# design.net
KiCad netlist of a schematic drawn in Altium Designer
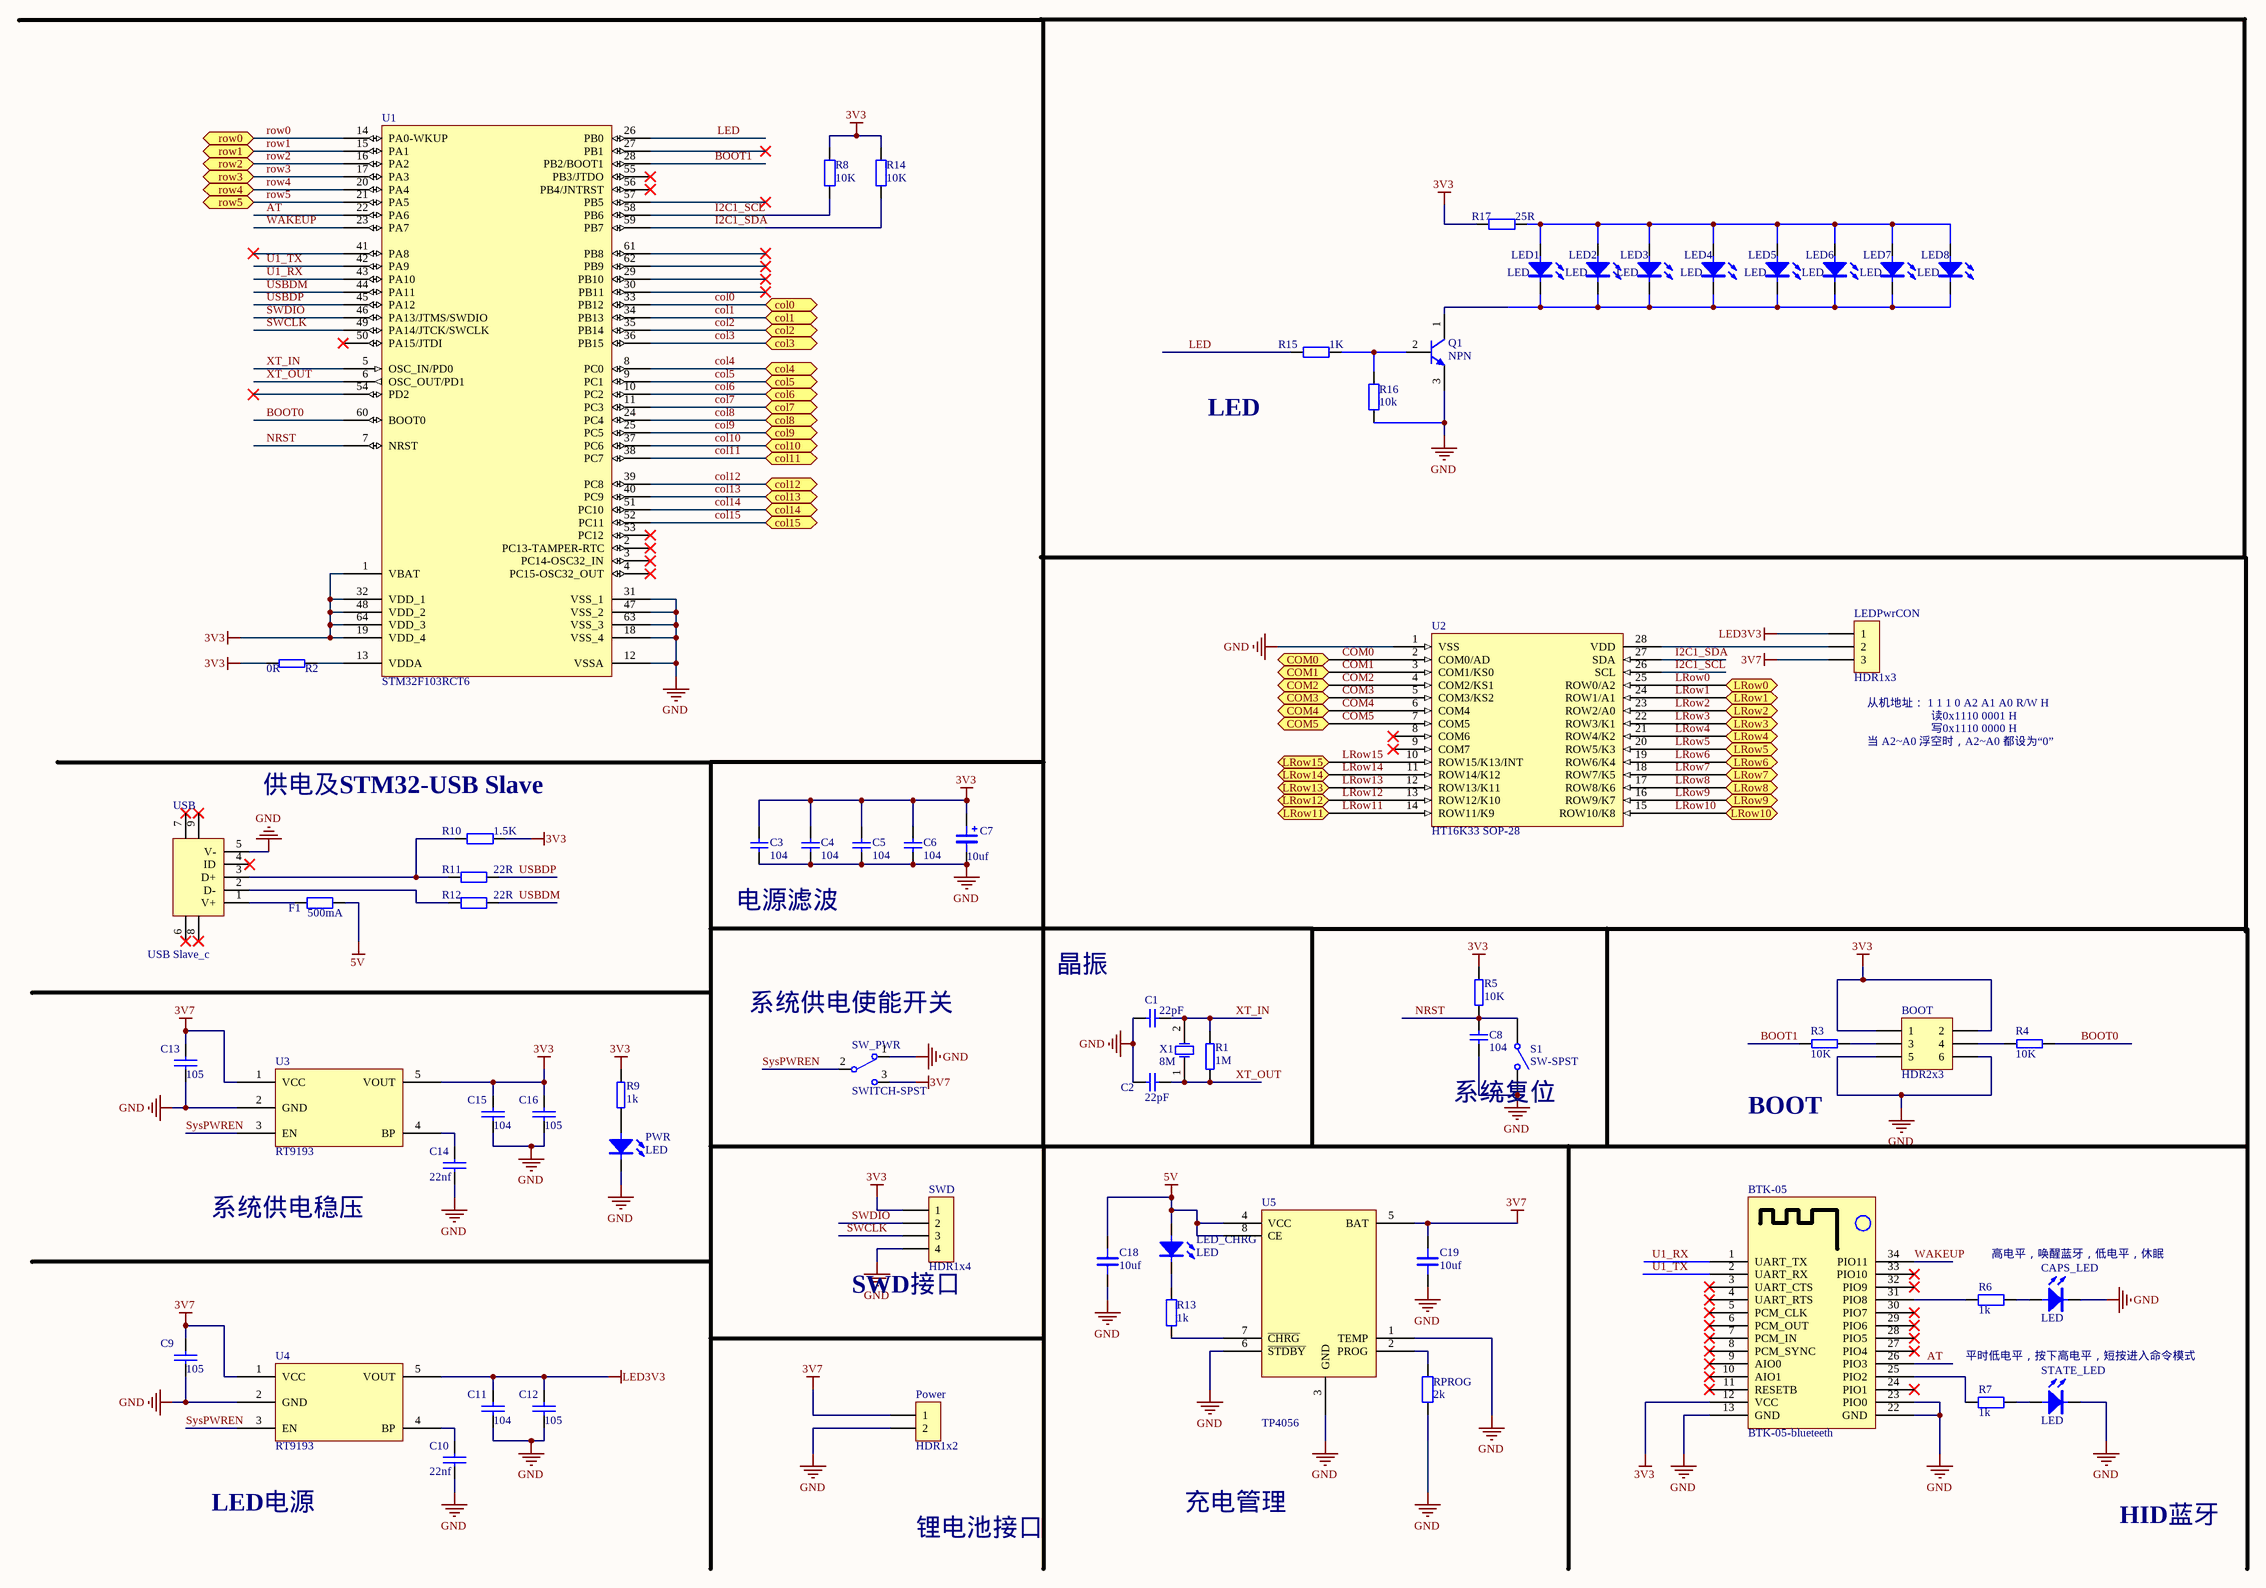
[diagram p0: 创世一号_主控.SchDoc]

(export (version "E")
  (design (tool "Eeschema 10.0.6"))
  (components
    (comp (ref "BOOT")
      (value "HDR2x3")
      (footprint "PIN-2x3-2.54-1.0")
      (description "Connector")
      (libsource (lib "General") (part "HDR2x3"))
    )
    (comp (ref "BTK-05")
      (value "BTK-05-blueteeth")
      (footprint "BTK-05-bluteeth")
      (libsource (lib "MyLib") (part "BTK-05-blueteeth"))
    )
    (comp (ref "C1")
      (value "22pF")
      (footprint "RC0603")
      (description "Capacitor")
      (fields (field (name "PUBLISHER") "ZL_A0OFFICE"))
      (libsource (lib "CommomDevices") (part "CAP1"))
    )
    (comp (ref "C2")
      (value "22pF")
      (footprint "RC0603")
      (description "Capacitor")
      (fields (field (name "PUBLISHER") "ZL_A0OFFICE"))
      (libsource (lib "CommomDevices") (part "CAP1"))
    )
    (comp (ref "C3")
      (value "104")
      (footprint "RC0603")
      (description "Capacitor")
      (fields (field (name "PUBLISHER") "ZL_A0OFFICE"))
      (libsource (lib "CommomDevices") (part "CAP1"))
    )
    (comp (ref "C4")
      (value "104")
      (footprint "RC0603")
      (description "Capacitor")
      (fields (field (name "PUBLISHER") "ZL_A0OFFICE"))
      (libsource (lib "CommomDevices") (part "CAP1"))
    )
    (comp (ref "C5")
      (value "104")
      (footprint "RC0603")
      (description "Capacitor")
      (fields (field (name "PUBLISHER") "ZL_A0OFFICE"))
      (libsource (lib "CommomDevices") (part "CAP1"))
    )
    (comp (ref "C6")
      (value "104")
      (footprint "RC0603")
      (description "Capacitor")
      (fields (field (name "PUBLISHER") "ZL_A0OFFICE"))
      (libsource (lib "CommomDevices") (part "CAP1"))
    )
    (comp (ref "C7")
      (value "10uf")
      (footprint "CAP0805")
      (description "Tantalum Capacitor")
      (libsource (lib "General") (part "CAP-TANTALUM"))
    )
    (comp (ref "C8")
      (value "104")
      (footprint "RC0603")
      (description "Capacitor")
      (fields (field (name "PUBLISHER") "ZL_A0OFFICE"))
      (libsource (lib "CommomDevices") (part "CAP1"))
    )
    (comp (ref "C9")
      (value "105")
      (footprint "0603")
      (description "Capacitor")
      (libsource (lib "*") (part "CAP"))
    )
    (comp (ref "C10")
      (value "22nf")
      (footprint "0603")
      (description "Capacitor")
      (libsource (lib "*") (part "CAP"))
    )
    (comp (ref "C11")
      (value "104")
      (footprint "0603")
      (description "Capacitor")
      (libsource (lib "*") (part "CAP"))
    )
    (comp (ref "C12")
      (value "105")
      (footprint "0603")
      (description "Capacitor")
      (libsource (lib "*") (part "CAP"))
    )
    (comp (ref "C13")
      (value "105")
      (footprint "0603")
      (description "Capacitor")
      (libsource (lib "*") (part "CAP"))
    )
    (comp (ref "C14")
      (value "22nf")
      (footprint "0603")
      (description "Capacitor")
      (libsource (lib "*") (part "CAP"))
    )
    (comp (ref "C15")
      (value "104")
      (footprint "0603")
      (description "Capacitor")
      (libsource (lib "*") (part "CAP"))
    )
    (comp (ref "C16")
      (value "105")
      (footprint "0603")
      (description "Capacitor")
      (libsource (lib "*") (part "CAP"))
    )
    (comp (ref "C18")
      (value "10uf")
      (footprint "0805")
      (description "Capacitor")
      (libsource (lib "General") (part "CAP"))
    )
    (comp (ref "C19")
      (value "10uf")
      (footprint "0805")
      (description "Capacitor")
      (libsource (lib "General") (part "CAP"))
    )
    (comp (ref "CAPS_LED") (value "LED") (footprint "LED-0805") (libsource (lib "General") (part "LED")))
    (comp (ref "F1")
      (value "500mA")
      (footprint "0805")
      (description "Resistor")
      (libsource (lib "") (part "Res2_1"))
    )
    (comp (ref "LED1") (value "LED") (footprint "LED-0805") (libsource (lib "General") (part "LED")))
    (comp (ref "LED2") (value "LED") (footprint "LED-0805") (libsource (lib "General") (part "LED")))
    (comp (ref "LED3") (value "LED") (footprint "LED-0805") (libsource (lib "General") (part "LED")))
    (comp (ref "LED4") (value "LED") (footprint "LED-0805") (libsource (lib "General") (part "LED")))
    (comp (ref "LED5") (value "LED") (footprint "LED-0805") (libsource (lib "General") (part "LED")))
    (comp (ref "LED6") (value "LED") (footprint "LED-0805") (libsource (lib "General") (part "LED")))
    (comp (ref "LED7") (value "LED") (footprint "LED-0805") (libsource (lib "General") (part "LED")))
    (comp (ref "LED8") (value "LED") (footprint "LED-0805") (libsource (lib "General") (part "LED")))
    (comp (ref "LEDPwrCON")
      (value "HDR1x3")
      (footprint "PIN-3-2.54-1.0")
      (description "Connector")
      (libsource (lib "General") (part "HDR1x3"))
    )
    (comp (ref "LED_CHRG") (value "LED") (footprint "LED-0805") (libsource (lib "General") (part "LED")))
    (comp (ref "Power")
      (value "HDR1x2")
      (footprint "PIN-2-2.54-1.0")
      (description "Connector")
      (libsource (lib "General") (part "HDR1x2"))
    )
    (comp (ref "PWR") (value "LED") (footprint "LED-0805") (libsource (lib "General") (part "LED")))
    (comp (ref "Q1")
      (value "NPN")
      (footprint "S8050-TO-92")
      (description "NPN Bipolar Transistor")
      (fields (field (name "PUBLISHER") "Altium Limited"))
      (libsource (lib "Miscellaneous Devices") (part "NPN"))
    )
    (comp (ref "R1") (value "1M") (footprint "RC0603") (libsource (lib "ZIBO V2.0_Main") (part "R")))
    (comp (ref "R2") (value "0R") (footprint "RC0603") (libsource (lib "ZIBO V2.0_Main") (part "R")))
    (comp (ref "R3") (value "10K") (footprint "RC0603") (libsource (lib "ZIBO V2.0_Main") (part "R")))
    (comp (ref "R4") (value "10K") (footprint "RC0603") (libsource (lib "ZIBO V2.0_Main") (part "R")))
    (comp (ref "R5") (value "10K") (footprint "RC0603") (libsource (lib "ZIBO V2.0_Main") (part "R")))
    (comp (ref "R6")
      (value "1k")
      (footprint "0603")
      (description "Resistor")
      (libsource (lib "") (part "RES_1"))
    )
    (comp (ref "R7")
      (value "1k")
      (footprint "0603")
      (description "Resistor")
      (libsource (lib "") (part "RES_1"))
    )
    (comp (ref "R8")
      (value "10K")
      (footprint "0603")
      (description "Resistor")
      (libsource (lib "") (part "Res2_2"))
    )
    (comp (ref "R9") (value "1k") (footprint "0603") (libsource (lib "ZIBO V2.0_Main") (part "R")))
    (comp (ref "R10")
      (value "1.5K")
      (footprint "0603")
      (description "Resistor")
      (libsource (lib "Miscellaneous Devices") (part "Res2"))
    )
    (comp (ref "R11")
      (value "22R")
      (footprint "0603")
      (description "Resistor")
      (libsource (lib "Miscellaneous Devices") (part "Res2"))
    )
    (comp (ref "R12")
      (value "22R")
      (footprint "0603")
      (description "Resistor")
      (libsource (lib "Miscellaneous Devices") (part "Res2"))
    )
    (comp (ref "R13")
      (value "1k")
      (footprint "0603")
      (description "Resistor")
      (libsource (lib "General") (part "RES"))
    )
    (comp (ref "R14")
      (value "10K")
      (footprint "0603")
      (description "Resistor")
      (libsource (lib "") (part "Res2_2"))
    )
    (comp (ref "R15")
      (value "1K")
      (footprint "0603")
      (description "Resistor")
      (libsource (lib "Miscellaneous Devices") (part "Res2"))
    )
    (comp (ref "R16")
      (value "10k")
      (footprint "0603")
      (description "Resistor")
      (libsource (lib "") (part "Res2_2"))
    )
    (comp (ref "R17")
      (value "25R")
      (footprint "0603")
      (description "Resistor")
      (libsource (lib "Miscellaneous Devices") (part "Res2"))
    )
    (comp (ref "RPROG")
      (value "2k")
      (footprint "0603")
      (description "Resistor")
      (libsource (lib "General") (part "RES"))
    )
    (comp (ref "S1")
      (value "SW-SPST")
      (footprint "SMT-KEY")
      (description "Single-Pole, Single-Throw Switch")
      (libsource (lib "Miscellaneous Devices") (part "SW-SPST"))
    )
    (comp (ref "STATE_LED") (value "LED") (footprint "LED-0805") (libsource (lib "General") (part "LED")))
    (comp (ref "SWD")
      (value "HDR1x4")
      (footprint "PIN-4-2.54-1.0")
      (description "Connector")
      (libsource (lib "General") (part "HDR1x4"))
    )
    (comp (ref "SW_PWR")
      (value "SWITCH-SPST")
      (footprint "Switch_3p_2.5mmjianju")
      (description "Switch")
      (libsource (lib "General") (part "SWITCH-SPST"))
    )
    (comp (ref "U1")
      (value "STM32F103RCT6")
      (footprint "QFP-64-0.5")
      (description "MCU")
      (libsource (lib "General") (part "STM32F103RxTx"))
    )
    (comp (ref "U2")
      (value "HT16K33 SOP-28")
      (footprint "HT16K33-28PIN-SOP28")
      (libsource (lib "MyLib") (part "HT16K33 SOP-28"))
    )
    (comp (ref "U3") (value "RT9193") (footprint "SOT-23-5") (libsource (lib "MyLib") (part "RT9193")))
    (comp (ref "U4") (value "RT9193") (footprint "SOT-23-5") (libsource (lib "MyLib") (part "RT9193")))
    (comp (ref "U5") (value "TP4056") (footprint "ESOP8") (libsource (lib "MyLib") (part "TP4056")))
    (comp (ref "USB")
      (value "USB Slave_c")
      (footprint "MICRO USB CONNECTOR TYPEB-ST-MC-5F-01")
      (description "USB Connector")
      (libsource (lib "General") (part "MICRO USB CONNECTOR TYPEB"))
    )
    (comp (ref "X1")
      (value "8M")
      (footprint "HC49-SMD")
      (description "Crystal Oscillator")
      (fields (field (name "PUBLISHER") "ZL_A0OFFICE"))
      (libsource (lib "CommomDevices") (part "XTAL_SMD"))
    )
  )
  (nets
    (net (code "1") (name "/AT") (class "Default")
      (node (ref "BTK-05") (pin "26") (pinfunction "PIO3_26") (pintype "passive"))
      (node (ref "U1") (pin "22") (pinfunction "PA6_22") (pintype "bidirectional"))
    )
    (net (code "2") (name "/BOOT0") (class "Default")
      (node (ref "R4") (pin "1") (pinfunction "1_1") (pintype "passive"))
      (node (ref "U1") (pin "60") (pinfunction "BOOT0_60") (pintype "bidirectional"))
    )
    (net (code "3") (name "/BOOT1") (class "Default")
      (node (ref "R3") (pin "2") (pinfunction "2_2") (pintype "passive"))
      (node (ref "U1") (pin "28") (pinfunction "PB2/BOOT1_28") (pintype "bidirectional"))
    )
    (net (code "4") (name "/COM0") (class "Default")
      (node (ref "U2") (pin "2") (pinfunction "COM0/AD_2") (pintype "input"))
    )
    (net (code "5") (name "/COM1") (class "Default")
      (node (ref "U2") (pin "3") (pinfunction "COM1/KS0_3") (pintype "input"))
    )
    (net (code "6") (name "/COM2") (class "Default")
      (node (ref "U2") (pin "4") (pinfunction "COM2/KS1_4") (pintype "input"))
    )
    (net (code "7") (name "/COM3") (class "Default")
      (node (ref "U2") (pin "5") (pinfunction "COM3/KS2_5") (pintype "input"))
    )
    (net (code "8") (name "/COM4") (class "Default")
      (node (ref "U2") (pin "6") (pinfunction "COM4_6") (pintype "input"))
    )
    (net (code "9") (name "/COM5") (class "Default")
      (node (ref "U2") (pin "7") (pinfunction "COM5_7") (pintype "input"))
    )
    (net (code "10") (name "/I2C1_SCL") (class "Default")
      (node (ref "R8") (pin "2") (pinfunction "2_2") (pintype "passive"))
      (node (ref "U1") (pin "58") (pinfunction "PB6_58") (pintype "bidirectional"))
      (node (ref "U2") (pin "26") (pinfunction "SCL_26") (pintype "input"))
    )
    (net (code "11") (name "/I2C1_SDA") (class "Default")
      (node (ref "R14") (pin "2") (pinfunction "2_2") (pintype "passive"))
      (node (ref "U1") (pin "59") (pinfunction "PB7_59") (pintype "bidirectional"))
      (node (ref "U2") (pin "27") (pinfunction "SDA_27") (pintype "input"))
    )
    (net (code "12") (name "/LED") (class "Default")
      (node (ref "R15") (pin "2") (pinfunction "2_2") (pintype "passive"))
      (node (ref "U1") (pin "26") (pinfunction "PB0_26") (pintype "bidirectional"))
    )
    (net (code "13") (name "/LRow0") (class "Default")
      (node (ref "U2") (pin "25") (pinfunction "ROW0/A2_25") (pintype "input"))
    )
    (net (code "14") (name "/LRow1") (class "Default")
      (node (ref "U2") (pin "24") (pinfunction "ROW1/A1_24") (pintype "input"))
    )
    (net (code "15") (name "/LRow2") (class "Default")
      (node (ref "U2") (pin "23") (pinfunction "ROW2/A0_23") (pintype "input"))
    )
    (net (code "16") (name "/LRow3") (class "Default")
      (node (ref "U2") (pin "22") (pinfunction "ROW3/K1_22") (pintype "input"))
    )
    (net (code "17") (name "/LRow4") (class "Default")
      (node (ref "U2") (pin "21") (pinfunction "ROW4/K2_21") (pintype "input"))
    )
    (net (code "18") (name "/LRow5") (class "Default")
      (node (ref "U2") (pin "20") (pinfunction "ROW5/K3_20") (pintype "input"))
    )
    (net (code "19") (name "/LRow6") (class "Default")
      (node (ref "U2") (pin "19") (pinfunction "ROW6/K4_19") (pintype "input"))
    )
    (net (code "20") (name "/LRow7") (class "Default")
      (node (ref "U2") (pin "18") (pinfunction "ROW7/K5_18") (pintype "input"))
    )
    (net (code "21") (name "/LRow8") (class "Default")
      (node (ref "U2") (pin "17") (pinfunction "ROW8/K6_17") (pintype "input"))
    )
    (net (code "22") (name "/LRow9") (class "Default")
      (node (ref "U2") (pin "16") (pinfunction "ROW9/K7_16") (pintype "input"))
    )
    (net (code "23") (name "/LRow10") (class "Default")
      (node (ref "U2") (pin "15") (pinfunction "ROW10/K8_15") (pintype "input"))
    )
    (net (code "24") (name "/LRow11") (class "Default")
      (node (ref "U2") (pin "14") (pinfunction "ROW11/K9_14") (pintype "input"))
    )
    (net (code "25") (name "/LRow12") (class "Default")
      (node (ref "U2") (pin "13") (pinfunction "ROW12/K10_13") (pintype "input"))
    )
    (net (code "26") (name "/LRow13") (class "Default")
      (node (ref "U2") (pin "12") (pinfunction "ROW13/K11_12") (pintype "input"))
    )
    (net (code "27") (name "/LRow14") (class "Default")
      (node (ref "U2") (pin "11") (pinfunction "ROW14/K12_11") (pintype "input"))
    )
    (net (code "28") (name "/LRow15") (class "Default")
      (node (ref "U2") (pin "10") (pinfunction "ROW15/K13/INT_10") (pintype "input"))
    )
    (net (code "29") (name "/NRST") (class "Default")
      (node (ref "C8") (pin "1") (pinfunction "1_1") (pintype "passive"))
      (node (ref "R5") (pin "1") (pinfunction "1_1") (pintype "passive"))
      (node (ref "S1") (pin "1") (pinfunction "COMMON_1") (pintype "passive"))
      (node (ref "U1") (pin "7") (pinfunction "NRST_7") (pintype "bidirectional"))
    )
    (net (code "30") (name "/SWCLK") (class "Default")
      (node (ref "SWD") (pin "3") (pinfunction "3_3") (pintype "passive"))
      (node (ref "U1") (pin "49") (pinfunction "PA14/JTCK/SWCLK_49") (pintype "bidirectional"))
    )
    (net (code "31") (name "/SWDIO") (class "Default")
      (node (ref "SWD") (pin "2") (pinfunction "2_2") (pintype "passive"))
      (node (ref "U1") (pin "46") (pinfunction "PA13/JTMS/SWDIO_46") (pintype "bidirectional"))
    )
    (net (code "32") (name "/SysPWREN") (class "Default")
      (node (ref "SW_PWR") (pin "2") (pinfunction "2_2") (pintype "passive"))
      (node (ref "U3") (pin "3") (pinfunction "EN_3") (pintype "passive"))
      (node (ref "U4") (pin "3") (pinfunction "EN_3") (pintype "passive"))
    )
    (net (code "33") (name "/U1_RX") (class "Default")
      (node (ref "BTK-05") (pin "1") (pinfunction "UART_TX_1") (pintype "passive"))
      (node (ref "U1") (pin "43") (pinfunction "PA10_43") (pintype "bidirectional"))
    )
    (net (code "34") (name "/U1_TX") (class "Default")
      (node (ref "BTK-05") (pin "2") (pinfunction "UART_RX_2") (pintype "passive"))
      (node (ref "U1") (pin "42") (pinfunction "PA9_42") (pintype "bidirectional"))
    )
    (net (code "35") (name "/USBDM") (class "Default")
      (node (ref "R12") (pin "1") (pinfunction "1_1") (pintype "passive"))
      (node (ref "U1") (pin "44") (pinfunction "PA11_44") (pintype "bidirectional"))
    )
    (net (code "36") (name "/USBDP") (class "Default")
      (node (ref "R11") (pin "1") (pinfunction "1_1") (pintype "passive"))
      (node (ref "U1") (pin "45") (pinfunction "PA12_45") (pintype "bidirectional"))
    )
    (net (code "37") (name "/WAKEUP") (class "Default")
      (node (ref "BTK-05") (pin "34") (pinfunction "PIO11_34") (pintype "passive"))
      (node (ref "U1") (pin "23") (pinfunction "PA7_23") (pintype "bidirectional"))
    )
    (net (code "38") (name "/XT_IN") (class "Default")
      (node (ref "C1") (pin "1") (pinfunction "1_1") (pintype "passive"))
      (node (ref "R1") (pin "2") (pinfunction "2_2") (pintype "passive"))
      (node (ref "U1") (pin "5") (pinfunction "OSC_IN/PD0_5") (pintype "input"))
      (node (ref "X1") (pin "2") (pinfunction "2_2") (pintype "passive"))
    )
    (net (code "39") (name "/XT_OUT") (class "Default")
      (node (ref "C2") (pin "1") (pinfunction "1_1") (pintype "passive"))
      (node (ref "R1") (pin "1") (pinfunction "1_1") (pintype "passive"))
      (node (ref "U1") (pin "6") (pinfunction "OSC_OUT/PD1_6") (pintype "output"))
      (node (ref "X1") (pin "1") (pinfunction "1_1") (pintype "passive"))
    )
    (net (code "40") (name "/col0") (class "Default")
      (node (ref "U1") (pin "33") (pinfunction "PB12_33") (pintype "bidirectional"))
    )
    (net (code "41") (name "/col1") (class "Default")
      (node (ref "U1") (pin "34") (pinfunction "PB13_34") (pintype "bidirectional"))
    )
    (net (code "42") (name "/col2") (class "Default")
      (node (ref "U1") (pin "35") (pinfunction "PB14_35") (pintype "bidirectional"))
    )
    (net (code "43") (name "/col3") (class "Default")
      (node (ref "U1") (pin "36") (pinfunction "PB15_36") (pintype "bidirectional"))
    )
    (net (code "44") (name "/col4") (class "Default")
      (node (ref "U1") (pin "8") (pinfunction "PC0_8") (pintype "bidirectional"))
    )
    (net (code "45") (name "/col5") (class "Default")
      (node (ref "U1") (pin "9") (pinfunction "PC1_9") (pintype "bidirectional"))
    )
    (net (code "46") (name "/col6") (class "Default")
      (node (ref "U1") (pin "10") (pinfunction "PC2_10") (pintype "bidirectional"))
    )
    (net (code "47") (name "/col7") (class "Default")
      (node (ref "U1") (pin "11") (pinfunction "PC3_11") (pintype "bidirectional"))
    )
    (net (code "48") (name "/col8") (class "Default")
      (node (ref "U1") (pin "24") (pinfunction "PC4_24") (pintype "bidirectional"))
    )
    (net (code "49") (name "/col9") (class "Default")
      (node (ref "U1") (pin "25") (pinfunction "PC5_25") (pintype "bidirectional"))
    )
    (net (code "50") (name "/col10") (class "Default")
      (node (ref "U1") (pin "37") (pinfunction "PC6_37") (pintype "bidirectional"))
    )
    (net (code "51") (name "/col11") (class "Default")
      (node (ref "U1") (pin "38") (pinfunction "PC7_38") (pintype "bidirectional"))
    )
    (net (code "52") (name "/col12") (class "Default")
      (node (ref "U1") (pin "39") (pinfunction "PC8_39") (pintype "bidirectional"))
    )
    (net (code "53") (name "/col13") (class "Default")
      (node (ref "U1") (pin "40") (pinfunction "PC9_40") (pintype "bidirectional"))
    )
    (net (code "54") (name "/col14") (class "Default")
      (node (ref "U1") (pin "51") (pinfunction "PC10_51") (pintype "bidirectional"))
    )
    (net (code "55") (name "/col15") (class "Default")
      (node (ref "U1") (pin "52") (pinfunction "PC11_52") (pintype "bidirectional"))
    )
    (net (code "56") (name "/row0") (class "Default")
      (node (ref "U1") (pin "14") (pinfunction "PA0-WKUP_14") (pintype "bidirectional"))
    )
    (net (code "57") (name "/row1") (class "Default")
      (node (ref "U1") (pin "15") (pinfunction "PA1_15") (pintype "bidirectional"))
    )
    (net (code "58") (name "/row2") (class "Default")
      (node (ref "U1") (pin "16") (pinfunction "PA2_16") (pintype "bidirectional"))
    )
    (net (code "59") (name "/row3") (class "Default")
      (node (ref "U1") (pin "17") (pinfunction "PA3_17") (pintype "bidirectional"))
    )
    (net (code "60") (name "/row4") (class "Default")
      (node (ref "U1") (pin "20") (pinfunction "PA4_20") (pintype "bidirectional"))
    )
    (net (code "61") (name "/row5") (class "Default")
      (node (ref "U1") (pin "21") (pinfunction "PA5_21") (pintype "bidirectional"))
    )
    (net (code "62") (name "3V3") (class "Default")
      (node (ref "BOOT") (pin "1") (pinfunction "1_1") (pintype "passive"))
      (node (ref "BOOT") (pin "2") (pinfunction "2_2") (pintype "passive"))
      (node (ref "BTK-05") (pin "12") (pinfunction "VCC_12") (pintype "passive"))
      (node (ref "C15") (pin "1") (pinfunction "1_1") (pintype "passive"))
      (node (ref "C16") (pin "1") (pinfunction "1_1") (pintype "passive"))
      (node (ref "C3") (pin "1") (pinfunction "1_1") (pintype "passive"))
      (node (ref "C4") (pin "1") (pinfunction "1_1") (pintype "passive"))
      (node (ref "C5") (pin "1") (pinfunction "1_1") (pintype "passive"))
      (node (ref "C6") (pin "1") (pinfunction "1_1") (pintype "passive"))
      (node (ref "C7") (pin "1") (pinfunction "1_1") (pintype "passive"))
      (node (ref "R10") (pin "1") (pinfunction "1_1") (pintype "passive"))
      (node (ref "R14") (pin "1") (pinfunction "1_1") (pintype "passive"))
      (node (ref "R17") (pin "2") (pinfunction "2_2") (pintype "passive"))
      (node (ref "R2") (pin "2") (pinfunction "2_2") (pintype "passive"))
      (node (ref "R5") (pin "2") (pinfunction "2_2") (pintype "passive"))
      (node (ref "R8") (pin "1") (pinfunction "1_1") (pintype "passive"))
      (node (ref "R9") (pin "2") (pinfunction "2_2") (pintype "passive"))
      (node (ref "SWD") (pin "1") (pinfunction "1_1") (pintype "passive"))
      (node (ref "U1") (pin "1") (pinfunction "VBAT_1") (pintype "power_in"))
      (node (ref "U1") (pin "19") (pinfunction "VDD_4_19") (pintype "power_in"))
      (node (ref "U1") (pin "32") (pinfunction "VDD_1_32") (pintype "power_in"))
      (node (ref "U1") (pin "48") (pinfunction "VDD_2_48") (pintype "power_in"))
      (node (ref "U1") (pin "64") (pinfunction "VDD_3_64") (pintype "power_in"))
      (node (ref "U3") (pin "5") (pinfunction "VOUT_5") (pintype "passive"))
    )
    (net (code "63") (name "3V7") (class "Default")
      (node (ref "C13") (pin "1") (pinfunction "1_1") (pintype "passive"))
      (node (ref "C19") (pin "2") (pinfunction "2_2") (pintype "passive"))
      (node (ref "C9") (pin "1") (pinfunction "1_1") (pintype "passive"))
      (node (ref "LEDPwrCON") (pin "3") (pinfunction "3_3") (pintype "passive"))
      (node (ref "Power") (pin "1") (pinfunction "1_1") (pintype "passive"))
      (node (ref "SW_PWR") (pin "3") (pinfunction "3_3") (pintype "passive"))
      (node (ref "U3") (pin "1") (pinfunction "VCC_1") (pintype "passive"))
      (node (ref "U4") (pin "1") (pinfunction "VCC_1") (pintype "passive"))
      (node (ref "U5") (pin "5") (pinfunction "BAT_5") (pintype "passive"))
    )
    (net (code "64") (name "5V") (class "Default")
      (node (ref "C18") (pin "2") (pinfunction "2_2") (pintype "passive"))
      (node (ref "F1") (pin "1") (pinfunction "1_1") (pintype "passive"))
      (node (ref "LED_CHRG") (pin "1") (pinfunction "A_1") (pintype "passive"))
      (node (ref "U5") (pin "4") (pinfunction "VCC_4") (pintype "passive"))
      (node (ref "U5") (pin "8") (pinfunction "CE_8") (pintype "passive"))
    )
    (net (code "65") (name "GND") (class "Default")
      (node (ref "BOOT") (pin "5") (pinfunction "5_5") (pintype "passive"))
      (node (ref "BOOT") (pin "6") (pinfunction "6_6") (pintype "passive"))
      (node (ref "BTK-05") (pin "13") (pinfunction "GND_13") (pintype "passive"))
      (node (ref "BTK-05") (pin "22") (pinfunction "GND_22") (pintype "passive"))
      (node (ref "BTK-05") (pin "23") (pinfunction "PIO0_23") (pintype "passive"))
      (node (ref "C1") (pin "2") (pinfunction "2_2") (pintype "passive"))
      (node (ref "C10") (pin "2") (pinfunction "2_2") (pintype "passive"))
      (node (ref "C11") (pin "2") (pinfunction "2_2") (pintype "passive"))
      (node (ref "C12") (pin "2") (pinfunction "2_2") (pintype "passive"))
      (node (ref "C13") (pin "2") (pinfunction "2_2") (pintype "passive"))
      (node (ref "C14") (pin "2") (pinfunction "2_2") (pintype "passive"))
      (node (ref "C15") (pin "2") (pinfunction "2_2") (pintype "passive"))
      (node (ref "C16") (pin "2") (pinfunction "2_2") (pintype "passive"))
      (node (ref "C18") (pin "1") (pinfunction "1_1") (pintype "passive"))
      (node (ref "C19") (pin "1") (pinfunction "1_1") (pintype "passive"))
      (node (ref "C2") (pin "2") (pinfunction "2_2") (pintype "passive"))
      (node (ref "C3") (pin "2") (pinfunction "2_2") (pintype "passive"))
      (node (ref "C4") (pin "2") (pinfunction "2_2") (pintype "passive"))
      (node (ref "C5") (pin "2") (pinfunction "2_2") (pintype "passive"))
      (node (ref "C6") (pin "2") (pinfunction "2_2") (pintype "passive"))
      (node (ref "C7") (pin "2") (pinfunction "2_2") (pintype "passive"))
      (node (ref "C8") (pin "2") (pinfunction "2_2") (pintype "passive"))
      (node (ref "C9") (pin "2") (pinfunction "2_2") (pintype "passive"))
      (node (ref "CAPS_LED") (pin "2") (pinfunction "C_2") (pintype "passive"))
      (node (ref "PWR") (pin "2") (pinfunction "C_2") (pintype "passive"))
      (node (ref "Power") (pin "2") (pinfunction "2_2") (pintype "passive"))
      (node (ref "Q1") (pin "3") (pinfunction "E_3") (pintype "passive"))
      (node (ref "R16") (pin "2") (pinfunction "2_2") (pintype "passive"))
      (node (ref "RPROG") (pin "1") (pinfunction "1_1") (pintype "passive"))
      (node (ref "S1") (pin "2") (pinfunction "NO_2") (pintype "passive"))
      (node (ref "STATE_LED") (pin "2") (pinfunction "C_2") (pintype "passive"))
      (node (ref "SWD") (pin "4") (pinfunction "4_4") (pintype "passive"))
      (node (ref "SW_PWR") (pin "1") (pinfunction "1_1") (pintype "passive"))
      (node (ref "U1") (pin "12") (pinfunction "VSSA_12") (pintype "power_in"))
      (node (ref "U1") (pin "18") (pinfunction "VSS_4_18") (pintype "power_in"))
      (node (ref "U1") (pin "31") (pinfunction "VSS_1_31") (pintype "power_in"))
      (node (ref "U1") (pin "47") (pinfunction "VSS_2_47") (pintype "power_in"))
      (node (ref "U1") (pin "63") (pinfunction "VSS_3_63") (pintype "power_in"))
      (node (ref "U2") (pin "1") (pinfunction "VSS_1") (pintype "input"))
      (node (ref "U3") (pin "2") (pinfunction "GND_2") (pintype "passive"))
      (node (ref "U4") (pin "2") (pinfunction "GND_2") (pintype "passive"))
      (node (ref "U5") (pin "1") (pinfunction "TEMP_1") (pintype "passive"))
      (node (ref "U5") (pin "3") (pinfunction "GND_3") (pintype "passive"))
      (node (ref "U5") (pin "6") (pinfunction "~{STDBY}_6") (pintype "passive"))
      (node (ref "USB") (pin "5") (pinfunction "V-_5") (pintype "passive"))
    )
    (net (code "66") (name "LED3V3") (class "Default")
      (node (ref "C11") (pin "1") (pinfunction "1_1") (pintype "passive"))
      (node (ref "C12") (pin "1") (pinfunction "1_1") (pintype "passive"))
      (node (ref "LEDPwrCON") (pin "1") (pinfunction "1_1") (pintype "passive"))
      (node (ref "U4") (pin "5") (pinfunction "VOUT_5") (pintype "passive"))
    )
    (net (code "67") (name "Net-(BOOT-Pad3)") (class "Default")
      (node (ref "BOOT") (pin "3") (pinfunction "3_3") (pintype "passive"))
      (node (ref "R3") (pin "1") (pinfunction "1_1") (pintype "passive"))
    )
    (net (code "68") (name "Net-(BOOT-Pad4)") (class "Default")
      (node (ref "BOOT") (pin "4") (pinfunction "4_4") (pintype "passive"))
      (node (ref "R4") (pin "2") (pinfunction "2_2") (pintype "passive"))
    )
    (net (code "69") (name "Net-(BTK-05-PIO2)") (class "Default")
      (node (ref "BTK-05") (pin "25") (pinfunction "PIO2_25") (pintype "passive"))
      (node (ref "R7") (pin "1") (pinfunction "1_1") (pintype "passive"))
    )
    (net (code "70") (name "Net-(BTK-05-PIO8)") (class "Default")
      (node (ref "BTK-05") (pin "31") (pinfunction "PIO8_31") (pintype "passive"))
      (node (ref "R6") (pin "1") (pinfunction "1_1") (pintype "passive"))
    )
    (net (code "71") (name "Net-(CAPS_LED-A)") (class "Default")
      (node (ref "CAPS_LED") (pin "1") (pinfunction "A_1") (pintype "passive"))
      (node (ref "R6") (pin "2") (pinfunction "2_2") (pintype "passive"))
    )
    (net (code "72") (name "Net-(LED1-A)") (class "Default")
      (node (ref "LED1") (pin "1") (pinfunction "A_1") (pintype "passive"))
      (node (ref "LED2") (pin "1") (pinfunction "A_1") (pintype "passive"))
      (node (ref "LED3") (pin "1") (pinfunction "A_1") (pintype "passive"))
      (node (ref "LED4") (pin "1") (pinfunction "A_1") (pintype "passive"))
      (node (ref "LED5") (pin "1") (pinfunction "A_1") (pintype "passive"))
      (node (ref "LED6") (pin "1") (pinfunction "A_1") (pintype "passive"))
      (node (ref "LED7") (pin "1") (pinfunction "A_1") (pintype "passive"))
      (node (ref "LED8") (pin "1") (pinfunction "A_1") (pintype "passive"))
      (node (ref "R17") (pin "1") (pinfunction "1_1") (pintype "passive"))
    )
    (net (code "73") (name "Net-(LED1-C)") (class "Default")
      (node (ref "LED1") (pin "2") (pinfunction "C_2") (pintype "passive"))
      (node (ref "LED2") (pin "2") (pinfunction "C_2") (pintype "passive"))
      (node (ref "LED3") (pin "2") (pinfunction "C_2") (pintype "passive"))
      (node (ref "LED4") (pin "2") (pinfunction "C_2") (pintype "passive"))
      (node (ref "LED5") (pin "2") (pinfunction "C_2") (pintype "passive"))
      (node (ref "LED6") (pin "2") (pinfunction "C_2") (pintype "passive"))
      (node (ref "LED7") (pin "2") (pinfunction "C_2") (pintype "passive"))
      (node (ref "LED8") (pin "2") (pinfunction "C_2") (pintype "passive"))
      (node (ref "Q1") (pin "1") (pinfunction "C_1") (pintype "passive"))
    )
    (net (code "74") (name "Net-(LED_CHRG-C)") (class "Default")
      (node (ref "LED_CHRG") (pin "2") (pinfunction "C_2") (pintype "passive"))
      (node (ref "R13") (pin "2") (pinfunction "2_2") (pintype "passive"))
    )
    (net (code "75") (name "Net-(PWR-A)") (class "Default")
      (node (ref "PWR") (pin "1") (pinfunction "A_1") (pintype "passive"))
      (node (ref "R9") (pin "1") (pinfunction "1_1") (pintype "passive"))
    )
    (net (code "76") (name "Net-(Q1-B)") (class "Default")
      (node (ref "Q1") (pin "2") (pinfunction "B_2") (pintype "passive"))
      (node (ref "R15") (pin "1") (pinfunction "1_1") (pintype "passive"))
      (node (ref "R16") (pin "1") (pinfunction "1_1") (pintype "passive"))
    )
    (net (code "77") (name "Net-(STATE_LED-A)") (class "Default")
      (node (ref "R7") (pin "2") (pinfunction "2_2") (pintype "passive"))
      (node (ref "STATE_LED") (pin "1") (pinfunction "A_1") (pintype "passive"))
    )
    (net (code "78") (name "Net-(U1-VDDA)") (class "Default")
      (node (ref "R2") (pin "1") (pinfunction "1_1") (pintype "passive"))
      (node (ref "U1") (pin "13") (pinfunction "VDDA_13") (pintype "power_in"))
    )
    (net (code "79") (name "Net-(U2-VDD)") (class "Default")
      (node (ref "LEDPwrCON") (pin "2") (pinfunction "2_2") (pintype "passive"))
      (node (ref "U2") (pin "28") (pinfunction "VDD_28") (pintype "power_in"))
    )
    (net (code "80") (name "Net-(U3-BP)") (class "Default")
      (node (ref "C14") (pin "1") (pinfunction "1_1") (pintype "passive"))
      (node (ref "U3") (pin "4") (pinfunction "BP_4") (pintype "passive"))
    )
    (net (code "81") (name "Net-(U4-BP)") (class "Default")
      (node (ref "C10") (pin "1") (pinfunction "1_1") (pintype "passive"))
      (node (ref "U4") (pin "4") (pinfunction "BP_4") (pintype "passive"))
    )
    (net (code "82") (name "Net-(U5-PROG)") (class "Default")
      (node (ref "RPROG") (pin "2") (pinfunction "2_2") (pintype "passive"))
      (node (ref "U5") (pin "2") (pinfunction "PROG_2") (pintype "passive"))
    )
    (net (code "83") (name "Net-(U5-~{CHRG})") (class "Default")
      (node (ref "R13") (pin "1") (pinfunction "1_1") (pintype "passive"))
      (node (ref "U5") (pin "7") (pinfunction "~{CHRG}_7") (pintype "passive"))
    )
    (net (code "84") (name "Net-(USB-D+)") (class "Default")
      (node (ref "R10") (pin "2") (pinfunction "2_2") (pintype "passive"))
      (node (ref "R11") (pin "2") (pinfunction "2_2") (pintype "passive"))
      (node (ref "USB") (pin "3") (pinfunction "D+_3") (pintype "passive"))
    )
    (net (code "85") (name "Net-(USB-D-)") (class "Default")
      (node (ref "R12") (pin "2") (pinfunction "2_2") (pintype "passive"))
      (node (ref "USB") (pin "2") (pinfunction "D-_2") (pintype "passive"))
    )
    (net (code "86") (name "Net-(USB-V+)") (class "Default")
      (node (ref "F1") (pin "2") (pinfunction "2_2") (pintype "passive"))
      (node (ref "USB") (pin "1") (pinfunction "V+_1") (pintype "passive"))
    )
    (net (code "87") (name "unconnected-(BTK-05-AIO0-Pad9)") (class "Default")
      (node (ref "BTK-05") (pin "9") (pinfunction "AIO0_9") (pintype "passive+no_connect"))
    )
    (net (code "88") (name "unconnected-(BTK-05-AIO1-Pad10)") (class "Default")
      (node (ref "BTK-05") (pin "10") (pinfunction "AIO1_10") (pintype "passive+no_connect"))
    )
    (net (code "89") (name "unconnected-(BTK-05-PCM_CLK-Pad5)") (class "Default")
      (node (ref "BTK-05") (pin "5") (pinfunction "PCM_CLK_5") (pintype "passive+no_connect"))
    )
    (net (code "90") (name "unconnected-(BTK-05-PCM_IN-Pad7)") (class "Default")
      (node (ref "BTK-05") (pin "7") (pinfunction "PCM_IN_7") (pintype "passive+no_connect"))
    )
    (net (code "91") (name "unconnected-(BTK-05-PCM_OUT-Pad6)") (class "Default")
      (node (ref "BTK-05") (pin "6") (pinfunction "PCM_OUT_6") (pintype "passive+no_connect"))
    )
    (net (code "92") (name "unconnected-(BTK-05-PCM_SYNC-Pad8)") (class "Default")
      (node (ref "BTK-05") (pin "8") (pinfunction "PCM_SYNC_8") (pintype "passive+no_connect"))
    )
    (net (code "93") (name "unconnected-(BTK-05-PIO1-Pad24)") (class "Default")
      (node (ref "BTK-05") (pin "24") (pinfunction "PIO1_24") (pintype "passive+no_connect"))
    )
    (net (code "94") (name "unconnected-(BTK-05-PIO4-Pad27)") (class "Default")
      (node (ref "BTK-05") (pin "27") (pinfunction "PIO4_27") (pintype "passive+no_connect"))
    )
    (net (code "95") (name "unconnected-(BTK-05-PIO5-Pad28)") (class "Default")
      (node (ref "BTK-05") (pin "28") (pinfunction "PIO5_28") (pintype "passive+no_connect"))
    )
    (net (code "96") (name "unconnected-(BTK-05-PIO6-Pad29)") (class "Default")
      (node (ref "BTK-05") (pin "29") (pinfunction "PIO6_29") (pintype "passive+no_connect"))
    )
    (net (code "97") (name "unconnected-(BTK-05-PIO7-Pad30)") (class "Default")
      (node (ref "BTK-05") (pin "30") (pinfunction "PIO7_30") (pintype "passive+no_connect"))
    )
    (net (code "98") (name "unconnected-(BTK-05-PIO9-Pad32)") (class "Default")
      (node (ref "BTK-05") (pin "32") (pinfunction "PIO9_32") (pintype "passive+no_connect"))
    )
    (net (code "99") (name "unconnected-(BTK-05-PIO10-Pad33)") (class "Default")
      (node (ref "BTK-05") (pin "33") (pinfunction "PIO10_33") (pintype "passive+no_connect"))
    )
    (net (code "100") (name "unconnected-(BTK-05-RESETB-Pad11)") (class "Default")
      (node (ref "BTK-05") (pin "11") (pinfunction "RESETB_11") (pintype "passive+no_connect"))
    )
    (net (code "101") (name "unconnected-(BTK-05-UART_CTS-Pad3)") (class "Default")
      (node (ref "BTK-05") (pin "3") (pinfunction "UART_CTS_3") (pintype "passive+no_connect"))
    )
    (net (code "102") (name "unconnected-(BTK-05-UART_RTS-Pad4)") (class "Default")
      (node (ref "BTK-05") (pin "4") (pinfunction "UART_RTS_4") (pintype "passive+no_connect"))
    )
    (net (code "103") (name "unconnected-(U1-PA8-Pad41)") (class "Default")
      (node (ref "U1") (pin "41") (pinfunction "PA8_41") (pintype "bidirectional+no_connect"))
    )
    (net (code "104") (name "unconnected-(U1-PA15{slash}JTDI-Pad50)") (class "Default")
      (node (ref "U1") (pin "50") (pinfunction "PA15/JTDI_50") (pintype "bidirectional+no_connect"))
    )
    (net (code "105") (name "unconnected-(U1-PB1-Pad27)") (class "Default")
      (node (ref "U1") (pin "27") (pinfunction "PB1_27") (pintype "bidirectional+no_connect"))
    )
    (net (code "106") (name "unconnected-(U1-PB3{slash}JTDO-Pad55)") (class "Default")
      (node (ref "U1") (pin "55") (pinfunction "PB3/JTDO_55") (pintype "bidirectional+no_connect"))
    )
    (net (code "107") (name "unconnected-(U1-PB4{slash}JNTRST-Pad56)") (class "Default")
      (node (ref "U1") (pin "56") (pinfunction "PB4/JNTRST_56") (pintype "bidirectional+no_connect"))
    )
    (net (code "108") (name "unconnected-(U1-PB5-Pad57)") (class "Default")
      (node (ref "U1") (pin "57") (pinfunction "PB5_57") (pintype "bidirectional+no_connect"))
    )
    (net (code "109") (name "unconnected-(U1-PB8-Pad61)") (class "Default")
      (node (ref "U1") (pin "61") (pinfunction "PB8_61") (pintype "bidirectional+no_connect"))
    )
    (net (code "110") (name "unconnected-(U1-PB9-Pad62)") (class "Default")
      (node (ref "U1") (pin "62") (pinfunction "PB9_62") (pintype "bidirectional+no_connect"))
    )
    (net (code "111") (name "unconnected-(U1-PB10-Pad29)") (class "Default")
      (node (ref "U1") (pin "29") (pinfunction "PB10_29") (pintype "bidirectional+no_connect"))
    )
    (net (code "112") (name "unconnected-(U1-PB11-Pad30)") (class "Default")
      (node (ref "U1") (pin "30") (pinfunction "PB11_30") (pintype "bidirectional+no_connect"))
    )
    (net (code "113") (name "unconnected-(U1-PC12-Pad53)") (class "Default")
      (node (ref "U1") (pin "53") (pinfunction "PC12_53") (pintype "bidirectional+no_connect"))
    )
    (net (code "114") (name "unconnected-(U1-PC13-TAMPER-RTC-Pad2)") (class "Default")
      (node (ref "U1") (pin "2") (pinfunction "PC13-TAMPER-RTC_2") (pintype "bidirectional+no_connect"))
    )
    (net (code "115") (name "unconnected-(U1-PC14-OSC32_IN-Pad3)") (class "Default")
      (node (ref "U1") (pin "3") (pinfunction "PC14-OSC32_IN_3") (pintype "bidirectional+no_connect"))
    )
    (net (code "116") (name "unconnected-(U1-PC15-OSC32_OUT-Pad4)") (class "Default")
      (node (ref "U1") (pin "4") (pinfunction "PC15-OSC32_OUT_4") (pintype "bidirectional+no_connect"))
    )
    (net (code "117") (name "unconnected-(U1-PD2-Pad54)") (class "Default")
      (node (ref "U1") (pin "54") (pinfunction "PD2_54") (pintype "bidirectional+no_connect"))
    )
    (net (code "118") (name "unconnected-(U2-COM6-Pad8)") (class "Default")
      (node (ref "U2") (pin "8") (pinfunction "COM6_8") (pintype "input+no_connect"))
    )
    (net (code "119") (name "unconnected-(U2-COM7-Pad9)") (class "Default")
      (node (ref "U2") (pin "9") (pinfunction "COM7_9") (pintype "input+no_connect"))
    )
    (net (code "120") (name "unconnected-(USB-ID-Pad4)") (class "Default")
      (node (ref "USB") (pin "4") (pinfunction "ID_4") (pintype "passive+no_connect"))
    )
    (net (code "121") (name "unconnected-(USB-Pad6)") (class "Default")
      (node (ref "USB") (pin "6") (pintype "passive+no_connect"))
    )
    (net (code "122") (name "unconnected-(USB-Pad7)") (class "Default")
      (node (ref "USB") (pin "7") (pintype "passive+no_connect"))
    )
    (net (code "123") (name "unconnected-(USB-Pad8)") (class "Default")
      (node (ref "USB") (pin "8") (pintype "passive+no_connect"))
    )
    (net (code "124") (name "unconnected-(USB-Pad9)") (class "Default")
      (node (ref "USB") (pin "9") (pintype "passive+no_connect"))
    )
  )
)
